# EthTInfo.net
KiCad netlist of a schematic drawn in EAGLE
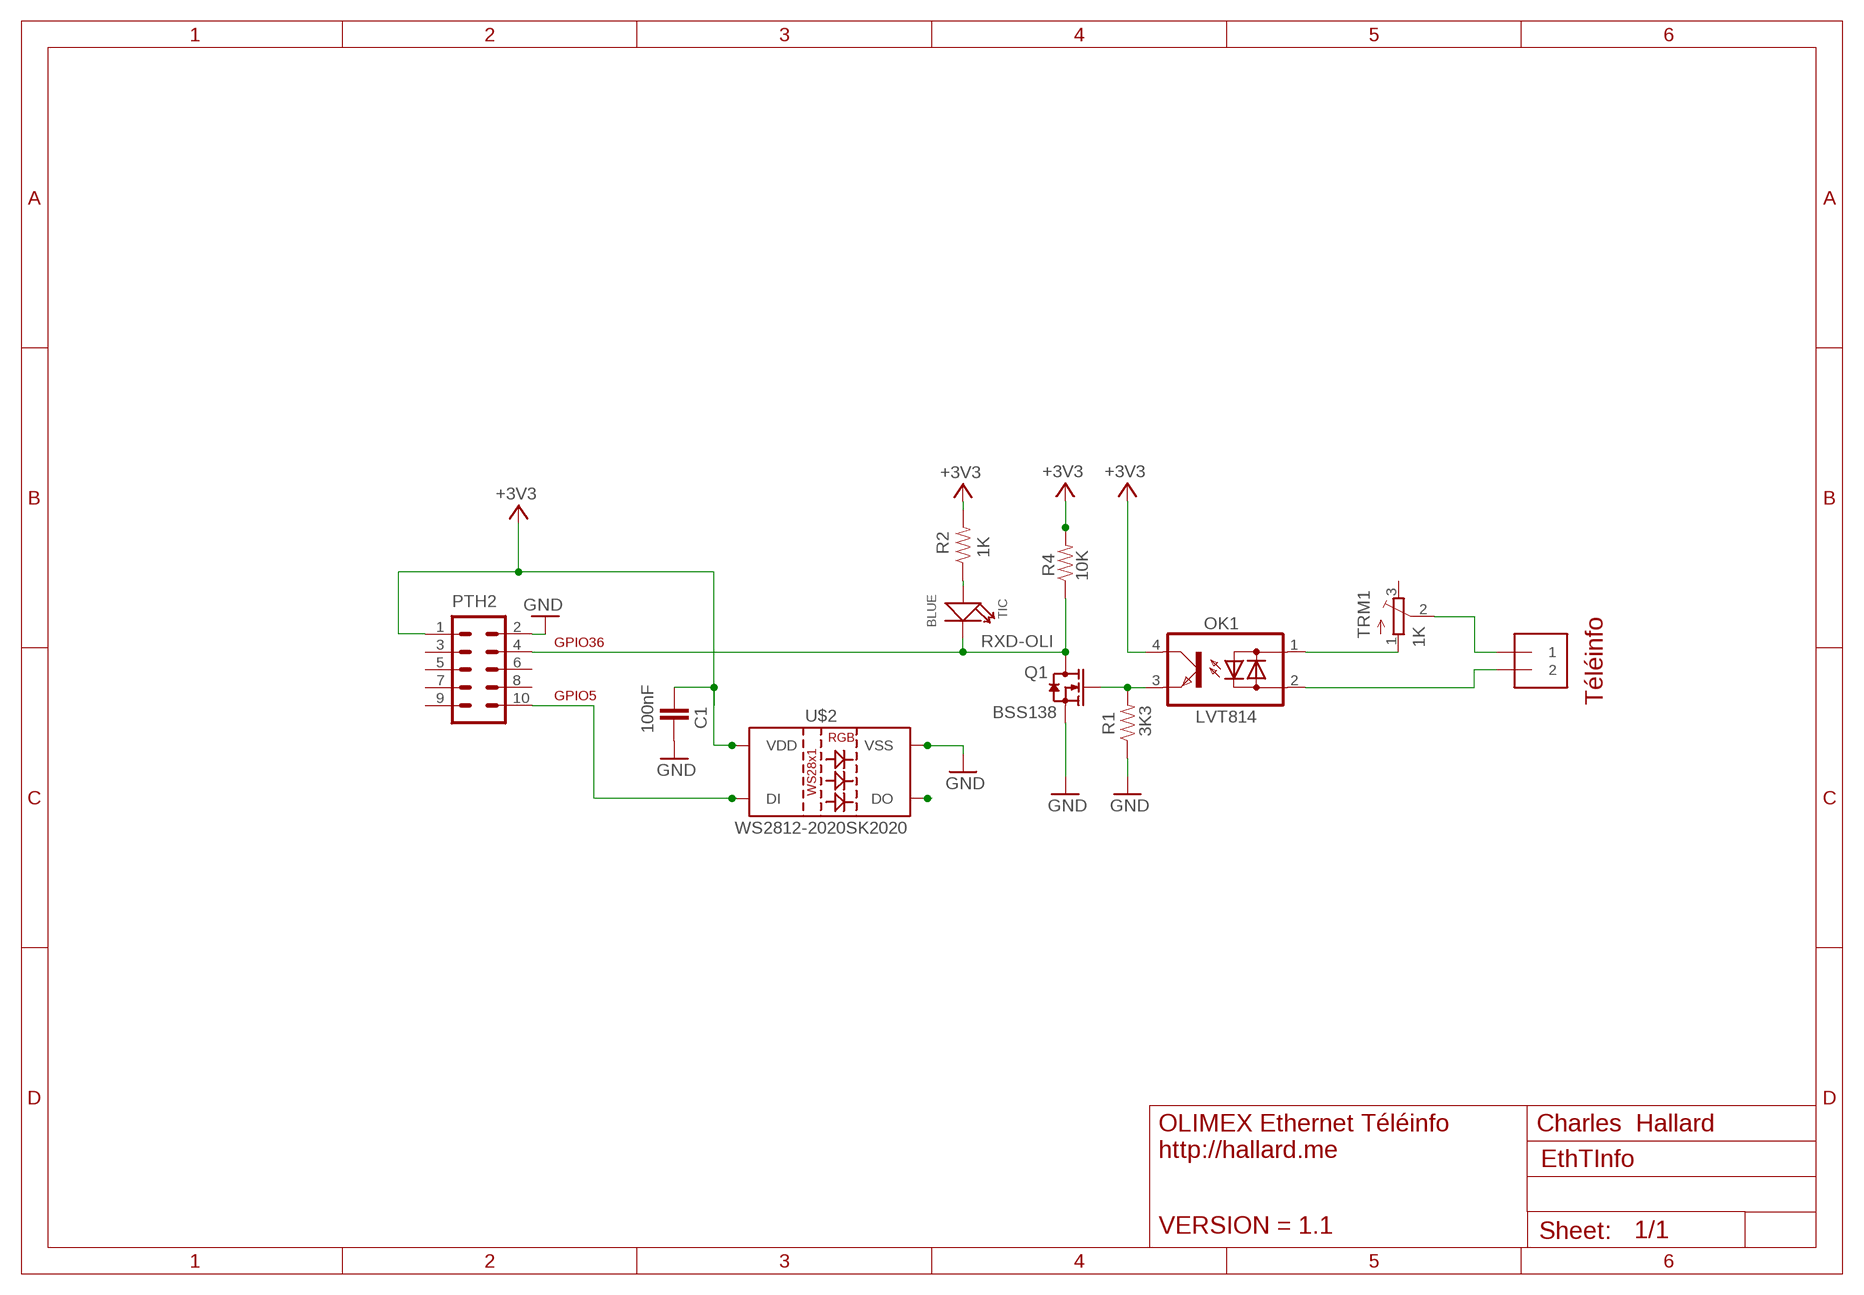
[diagram p0: schematic, sheet 1]

(export (version "E")
  (design (tool "Eeschema 10.0.6"))
  (components
    (comp (ref "C1")
      (value "100nF")
      (footprint "eagle-import:0402-CAP-OK")
      (libsource (lib "eagle-import") (part "CAP0402-CAP-OK"))
    )
    (comp (ref "J1")
      (value "1X2-3.5MM-3.5MM")
      (footprint "eagle-import:1X2-3.5MM")
      (libsource (lib "eagle-import") (part "1X2-3.5MM-3.5MM"))
    )
    (comp (ref "OK1")
      (value "LVT814")
      (footprint "eagle-import:DIL4-SMD")
      (fields (field (name "MF") "VISHAY/TELEFUNKEN") (field (name "MPN") "SFH6206-3"))
      (libsource (lib "eagle-import") (part "SFH6206"))
    )
    (comp (ref "PTH2")
      (value "ML10FEMALE")
      (footprint "eagle-import:ML10-FEMALE")
      (libsource (lib "eagle-import") (part "ML10FEMALE"))
    )
    (comp (ref "Q1")
      (value "BSS138")
      (footprint "eagle-import:SOT-323-3")
      (libsource (lib "eagle-import") (part "SMD-MOSFET-N-CH-20V-2.1A-CJ2302(SOT-23)"))
    )
    (comp (ref "R1")
      (value "3K3")
      (footprint "eagle-import:0402-RES")
      (libsource (lib "eagle-import") (part "RESISTOR0402-RES"))
    )
    (comp (ref "R2")
      (value "1K")
      (footprint "eagle-import:0402-RES")
      (libsource (lib "eagle-import") (part "RESISTOR0402-RES"))
    )
    (comp (ref "R4")
      (value "10K")
      (footprint "eagle-import:0402-RES")
      (libsource (lib "eagle-import") (part "RESISTOR0402-RES"))
    )
    (comp (ref "TIC")
      (value "BLUE")
      (footprint "eagle-import:LED-0402")
      (fields (field (name "MPN") "BL-HB337A-AV-TRB"))
      (libsource (lib "eagle-import") (part "SMD-LED-CLEAR-BLUE(0402)"))
    )
    (comp (ref "TRM1")
      (value "1K")
      (footprint "eagle-import:TC33X")
      (libsource (lib "eagle-import") (part "TRIMPOTTC33X"))
    )
    (comp (ref "U$2")
      (value "WS2812-2020SK2020")
      (footprint "eagle-import:SK6805-2020")
      (libsource (lib "eagle-import") (part "WS2812-2020SK2020"))
    )
  )
  (nets
    (net (code "1") (name "+3V3") (class "Default")
      (node (ref "C1") (pin "2") (pinfunction "2_2") (pintype "passive"))
      (node (ref "OK1") (pin "4") (pinfunction "C_4") (pintype "passive"))
      (node (ref "PTH2") (pin "1") (pinfunction "1_1") (pintype "passive"))
      (node (ref "R2") (pin "2") (pinfunction "2_2") (pintype "passive"))
      (node (ref "R4") (pin "2") (pinfunction "2_2") (pintype "passive"))
      (node (ref "U$2") (pin "1") (pinfunction "VDD_1") (pintype "bidirectional"))
    )
    (net (code "2") (name "/RXD-OLI") (class "Default")
      (node (ref "PTH2") (pin "4") (pinfunction "4_4") (pintype "passive"))
      (node (ref "Q1") (pin "3") (pinfunction "D_3") (pintype "passive"))
      (node (ref "R4") (pin "1") (pinfunction "1_1") (pintype "passive"))
      (node (ref "TIC") (pin "-") (pinfunction "-_-") (pintype "passive"))
    )
    (net (code "3") (name "GND") (class "Default")
      (node (ref "C1") (pin "1") (pinfunction "1_1") (pintype "passive"))
      (node (ref "PTH2") (pin "2") (pinfunction "2_2") (pintype "passive"))
      (node (ref "Q1") (pin "2") (pinfunction "S_2") (pintype "passive"))
      (node (ref "R1") (pin "1") (pinfunction "1_1") (pintype "passive"))
      (node (ref "U$2") (pin "3") (pinfunction "VSS_3") (pintype "bidirectional"))
    )
    (net (code "4") (name "Net-(OK1-AC1)") (class "Default")
      (node (ref "OK1") (pin "1") (pinfunction "AC1_1") (pintype "passive"))
      (node (ref "TRM1") (pin "1") (pinfunction "A_1") (pintype "passive"))
    )
    (net (code "5") (name "Net-(OK1-AC2)") (class "Default")
      (node (ref "J1") (pin "2") (pinfunction "2_2") (pintype "passive"))
      (node (ref "OK1") (pin "2") (pinfunction "AC2_2") (pintype "passive"))
    )
    (net (code "6") (name "Net-(OK1-E)") (class "Default")
      (node (ref "OK1") (pin "3") (pinfunction "E_3") (pintype "passive"))
      (node (ref "Q1") (pin "1") (pinfunction "G_1") (pintype "passive"))
      (node (ref "R1") (pin "2") (pinfunction "2_2") (pintype "passive"))
    )
    (net (code "7") (name "Net-(R2-Pad1)") (class "Default")
      (node (ref "R2") (pin "1") (pinfunction "1_1") (pintype "passive"))
      (node (ref "TIC") (pin "+") (pinfunction "+_+") (pintype "passive"))
    )
    (net (code "8") (name "Net-(TRM1-S)") (class "Default")
      (node (ref "J1") (pin "1") (pinfunction "1_1") (pintype "passive"))
      (node (ref "TRM1") (pin "2") (pinfunction "S_2") (pintype "passive"))
    )
    (net (code "9") (name "Net-(U$2-DI)") (class "Default")
      (node (ref "PTH2") (pin "10") (pinfunction "10_10") (pintype "passive"))
      (node (ref "U$2") (pin "4") (pinfunction "DI_4") (pintype "bidirectional"))
    )
    (net (code "10") (name "unconnected-(PTH2-Pad3)") (class "Default")
      (node (ref "PTH2") (pin "3") (pinfunction "3_3") (pintype "passive"))
    )
    (net (code "11") (name "unconnected-(PTH2-Pad5)") (class "Default")
      (node (ref "PTH2") (pin "5") (pinfunction "5_5") (pintype "passive"))
    )
    (net (code "12") (name "unconnected-(PTH2-Pad6)") (class "Default")
      (node (ref "PTH2") (pin "6") (pinfunction "6_6") (pintype "passive"))
    )
    (net (code "13") (name "unconnected-(PTH2-Pad7)") (class "Default")
      (node (ref "PTH2") (pin "7") (pinfunction "7_7") (pintype "passive"))
    )
    (net (code "14") (name "unconnected-(PTH2-Pad8)") (class "Default")
      (node (ref "PTH2") (pin "8") (pinfunction "8_8") (pintype "passive"))
    )
    (net (code "15") (name "unconnected-(PTH2-Pad9)") (class "Default")
      (node (ref "PTH2") (pin "9") (pinfunction "9_9") (pintype "passive"))
    )
    (net (code "16") (name "unconnected-(TRM1-E-Pad3)") (class "Default")
      (node (ref "TRM1") (pin "3") (pinfunction "E_3") (pintype "passive"))
    )
    (net (code "17") (name "unconnected-(U$2-DO-Pad2)") (class "Default")
      (node (ref "U$2") (pin "2") (pinfunction "DO_2") (pintype "bidirectional"))
    )
  )
)
